# OledBoardV3.net
KiCad netlist of a schematic drawn in EAGLE
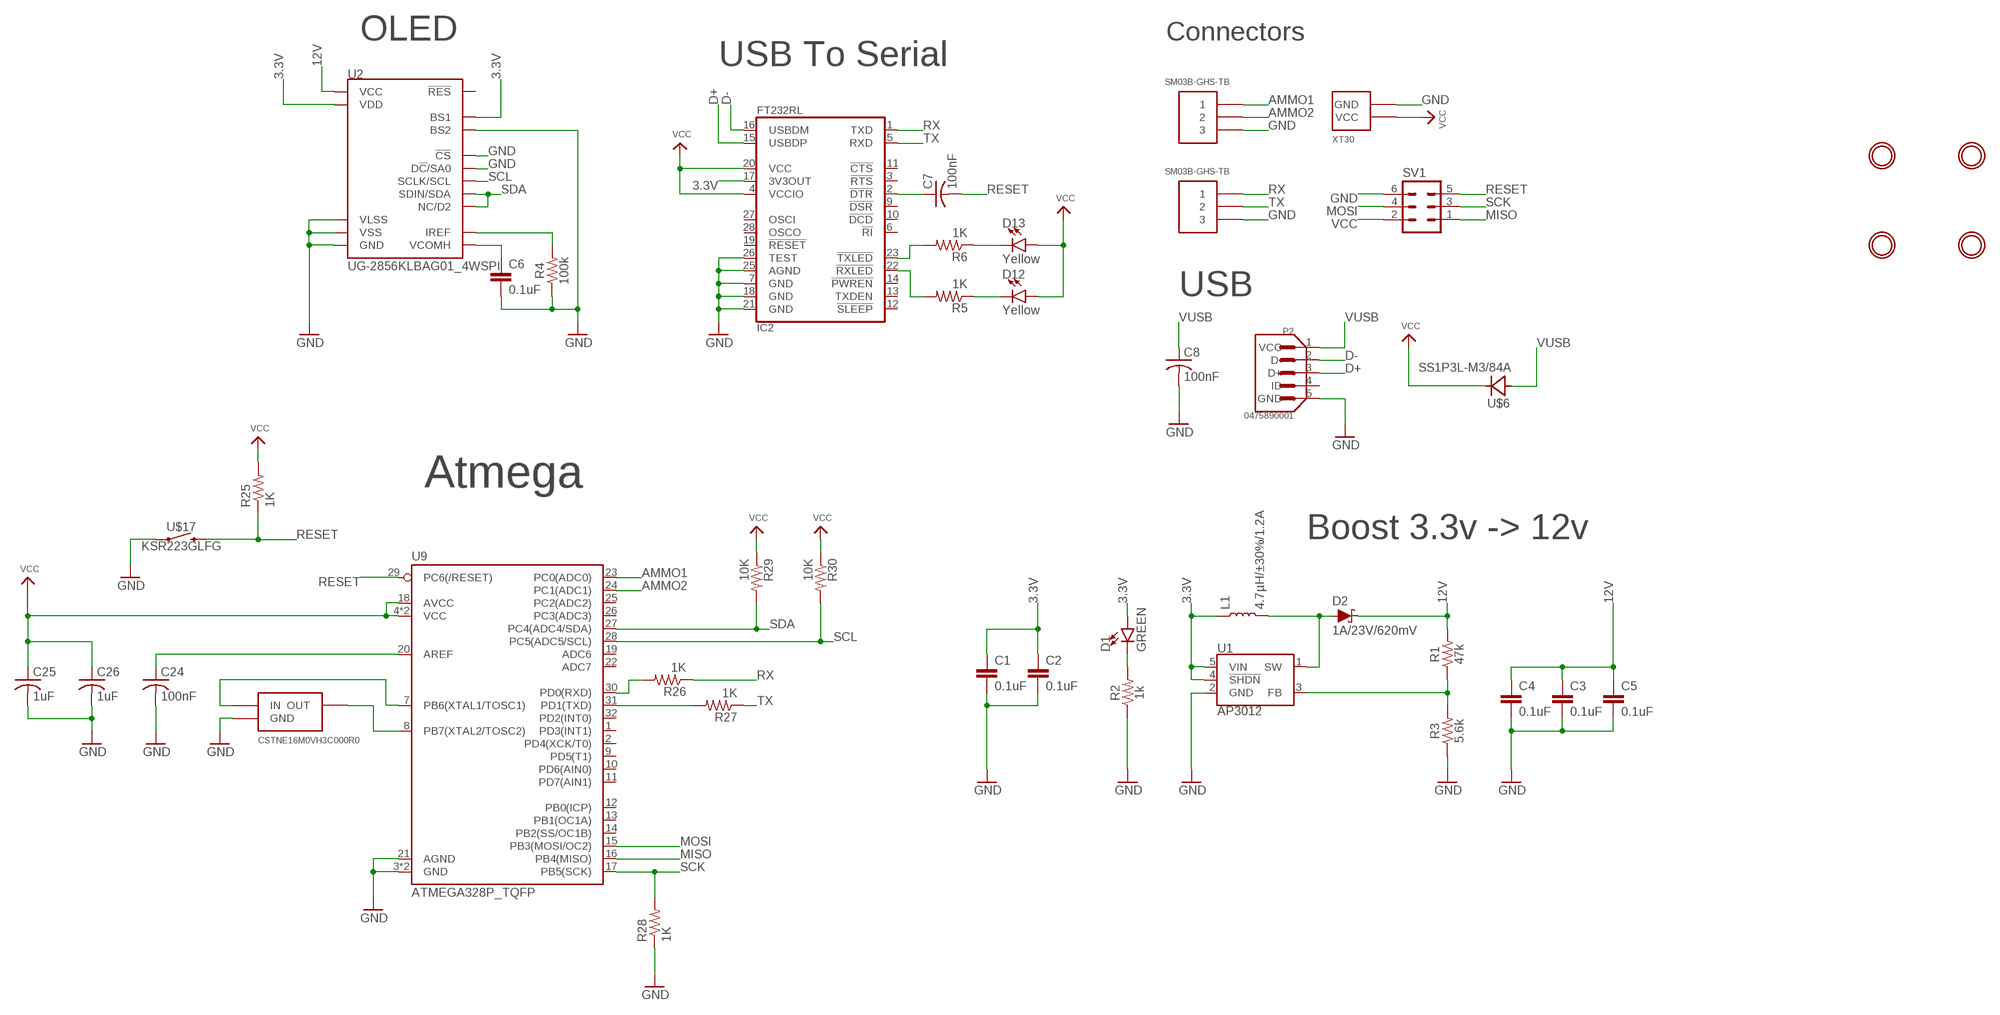
[diagram p0: schematic, sheet 1]

(export (version "E")
  (design (tool "Eeschema 10.0.6"))
  (components
    (comp (ref "C1")
      (value "0.1uF")
      (footprint "eagle-import:0603")
      (libsource (lib "eagle-import") (part "0.1UF-0603-25V-(+80/-20%)"))
    )
    (comp (ref "C2")
      (value "0.1uF")
      (footprint "eagle-import:0603")
      (libsource (lib "eagle-import") (part "0.1UF-0603-25V-(+80/-20%)"))
    )
    (comp (ref "C3")
      (value "0.1uF")
      (footprint "eagle-import:0603")
      (libsource (lib "eagle-import") (part "0.1UF-0603-25V-(+80/-20%)"))
    )
    (comp (ref "C4")
      (value "0.1uF")
      (footprint "eagle-import:0603")
      (libsource (lib "eagle-import") (part "0.1UF-0603-25V-(+80/-20%)"))
    )
    (comp (ref "C5")
      (value "0.1uF")
      (footprint "eagle-import:0603")
      (libsource (lib "eagle-import") (part "0.1UF-0603-25V-(+80/-20%)"))
    )
    (comp (ref "C6")
      (value "0.1uF")
      (footprint "eagle-import:0603")
      (libsource (lib "eagle-import") (part "0.1UF-0603-25V-(+80/-20%)"))
    )
    (comp (ref "C7")
      (value "100nF")
      (footprint "eagle-import:C0603")
      (libsource (lib "eagle-import") (part "C-USC0603"))
    )
    (comp (ref "C8")
      (value "100nF")
      (footprint "eagle-import:C0603")
      (libsource (lib "eagle-import") (part "C-USC0603"))
    )
    (comp (ref "C24")
      (value "100nF")
      (footprint "eagle-import:C0603")
      (libsource (lib "eagle-import") (part "C-USC0603"))
    )
    (comp (ref "C25")
      (value "1uF")
      (footprint "eagle-import:C0603")
      (libsource (lib "eagle-import") (part "C-USC0603"))
    )
    (comp (ref "C26")
      (value "1uF")
      (footprint "eagle-import:C0603")
      (libsource (lib "eagle-import") (part "C-USC0603"))
    )
    (comp (ref "D1")
      (value "GREEN")
      (footprint "eagle-import:LED-0603")
      (libsource (lib "eagle-import") (part "SparkFun-LED_529_LED0603"))
    )
    (comp (ref "D2")
      (value "1A/23V/620mV")
      (footprint "eagle-import:SOD-323")
      (libsource (lib "eagle-import") (part "DIODE-SCHOTTKY-BAT20J"))
    )
    (comp (ref "D12")
      (value "Yellow")
      (footprint "eagle-import:LED-0603")
      (libsource (lib "eagle-import") (part "LED0603"))
    )
    (comp (ref "D13")
      (value "Yellow")
      (footprint "eagle-import:LED-0603")
      (libsource (lib "eagle-import") (part "LED0603"))
    )
    (comp (ref "IC2")
      (value "FT232RL")
      (footprint "eagle-import:SSOP28-LD")
      (fields (field (name "DIGI-KEY_PART_NUMBER") "768-1007-1-ND") (field (name "MF") "FTDI, Future"))
      (libsource (lib "eagle-import") (part "FT232RL"))
    )
    (comp (ref "L1")
      (value "4.7µH/±30%/1.2A")
      (footprint "eagle-import:INDUCTOR_4.7UH")
      (libsource (lib "eagle-import") (part "INDUCTOR-CDRH-4.7UH"))
    )
    (comp (ref "P2")
      (value "0475890001")
      (footprint "eagle-import:MOLEX_0475890001")
      (fields (field (name "DIGI-KEY_PART_NUMBER") "WM17143CT-ND") (field (name "MF") "Molex"))
      (libsource (lib "eagle-import") (part "0475890001"))
    )
    (comp (ref "R1")
      (value "47k")
      (footprint "eagle-import:0603")
      (libsource (lib "eagle-import") (part "47KOHM-0603-1/10W-1%"))
    )
    (comp (ref "R2")
      (value "1k")
      (footprint "eagle-import:0603")
      (libsource (lib "eagle-import") (part "1KOHM-0603-1/10W-1%"))
    )
    (comp (ref "R3")
      (value "5.6k")
      (footprint "eagle-import:0603")
      (libsource (lib "eagle-import") (part "5.6KOHM-0603-1/10W-1%"))
    )
    (comp (ref "R4")
      (value "100k")
      (footprint "eagle-import:0603")
      (libsource (lib "eagle-import") (part "100KOHM-0603-1/10W-1%"))
    )
    (comp (ref "R5")
      (value "1K")
      (footprint "eagle-import:R0603")
      (libsource (lib "eagle-import") (part "R-US_R0603"))
    )
    (comp (ref "R6")
      (value "1K")
      (footprint "eagle-import:R0603")
      (libsource (lib "eagle-import") (part "R-US_R0603"))
    )
    (comp (ref "R25")
      (value "1K")
      (footprint "eagle-import:R0603")
      (libsource (lib "eagle-import") (part "R-US_R0603"))
    )
    (comp (ref "R26")
      (value "1K")
      (footprint "eagle-import:R0603")
      (libsource (lib "eagle-import") (part "R-US_R0603"))
    )
    (comp (ref "R27")
      (value "1K")
      (footprint "eagle-import:R0603")
      (libsource (lib "eagle-import") (part "R-US_R0603"))
    )
    (comp (ref "R28")
      (value "1K")
      (footprint "eagle-import:R0603")
      (libsource (lib "eagle-import") (part "R-US_R0603"))
    )
    (comp (ref "R29")
      (value "10K")
      (footprint "eagle-import:R0603")
      (libsource (lib "eagle-import") (part "R-US_R0603"))
    )
    (comp (ref "R30")
      (value "10K")
      (footprint "eagle-import:R0603")
      (libsource (lib "eagle-import") (part "R-US_R0603"))
    )
    (comp (ref "SV1")
      (value "MA03-2")
      (footprint "eagle-import:MA03-2")
      (libsource (lib "eagle-import") (part "MA03-2"))
    )
    (comp (ref "U$1")
      (value "MOUNTINGHOLE2.5")
      (footprint "eagle-import:MOUNTINGHOLE_2.5_PLATED")
      (libsource (lib "eagle-import") (part "MOUNTINGHOLE2.5"))
    )
    (comp (ref "U$2")
      (value "MOUNTINGHOLE2.5")
      (footprint "eagle-import:MOUNTINGHOLE_2.5_PLATED")
      (libsource (lib "eagle-import") (part "MOUNTINGHOLE2.5"))
    )
    (comp (ref "U$3")
      (value "MOUNTINGHOLE2.5")
      (footprint "eagle-import:MOUNTINGHOLE_2.5_PLATED")
      (libsource (lib "eagle-import") (part "MOUNTINGHOLE2.5"))
    )
    (comp (ref "U$4")
      (value "MOUNTINGHOLE2.5")
      (footprint "eagle-import:MOUNTINGHOLE_2.5_PLATED")
      (libsource (lib "eagle-import") (part "MOUNTINGHOLE2.5"))
    )
    (comp (ref "U$5")
      (value "SM03B-GHS-TB")
      (footprint "eagle-import:SM03B-GHS-TB")
      (libsource (lib "eagle-import") (part "SM03B-GHS-TB"))
    )
    (comp (ref "U$6")
      (value "SS1P3L-M3/84A")
      (footprint "eagle-import:SS1P3L-M3_84A")
      (libsource (lib "eagle-import") (part "SS1P3L-M3/84A"))
    )
    (comp (ref "U$8")
      (value "SM03B-GHS-TB")
      (footprint "eagle-import:SM03B-GHS-TB")
      (libsource (lib "eagle-import") (part "SM03B-GHS-TB"))
    )
    (comp (ref "U$9")
      (value "XT30PW-M")
      (footprint "eagle-import:XT30")
      (libsource (lib "eagle-import") (part "XT30PW-M"))
    )
    (comp (ref "U$16")
      (value "CSTNE16M0VH3C000R0")
      (footprint "eagle-import:CSTNE16M0VH3C000R0")
      (libsource (lib "eagle-import") (part "CSTNE16M0VH3C000R0"))
    )
    (comp (ref "U$17")
      (value "KSR223GLFG")
      (footprint "eagle-import:KSR223GLFG")
      (libsource (lib "eagle-import") (part "KSR223GLFG"))
    )
    (comp (ref "U1")
      (value "AP3012")
      (footprint "eagle-import:SOT23-5")
      (libsource (lib "eagle-import") (part "AP3012"))
    )
    (comp (ref "U2")
      (value "UG-2856KLBAG01_4WSPI")
      (footprint "eagle-import:FPC05024-42201")
      (libsource (lib "eagle-import") (part "UG-2856KLBAG01_4WSPI"))
    )
    (comp (ref "U9")
      (value "ATMEGA328P_TQFP")
      (footprint "eagle-import:TQFP32-08")
      (libsource (lib "eagle-import") (part "ATMEGA328P_TQFP"))
    )
  )
  (nets
    (net (code "1") (name "/3.3V") (class "Default")
      (node (ref "C1") (pin "1") (pinfunction "1_1") (pintype "passive"))
      (node (ref "C2") (pin "1") (pinfunction "1_1") (pintype "passive"))
      (node (ref "D1") (pin "A") (pinfunction "A_A") (pintype "passive"))
      (node (ref "IC2") (pin "17") (pinfunction "3V3OUT_17") (pintype "power_in"))
      (node (ref "L1") (pin "P$1") (pinfunction "1_P$1") (pintype "passive"))
      (node (ref "U1") (pin "4") (pinfunction "~{SHDN}_4") (pintype "bidirectional"))
      (node (ref "U1") (pin "5") (pinfunction "VIN_5") (pintype "bidirectional"))
      (node (ref "U2") (pin "P$5") (pinfunction "VDD_P$5") (pintype "bidirectional"))
      (node (ref "U2") (pin "P$6") (pinfunction "BS1_P$6") (pintype "bidirectional"))
    )
    (net (code "2") (name "/12V") (class "Default")
      (node (ref "C3") (pin "1") (pinfunction "1_1") (pintype "passive"))
      (node (ref "C4") (pin "1") (pinfunction "1_1") (pintype "passive"))
      (node (ref "C5") (pin "1") (pinfunction "1_1") (pintype "passive"))
      (node (ref "D2") (pin "C") (pinfunction "C_C") (pintype "passive"))
      (node (ref "R1") (pin "2") (pinfunction "2_2") (pintype "passive"))
      (node (ref "U2") (pin "P$23") (pinfunction "VCC_P$23") (pintype "bidirectional"))
    )
    (net (code "3") (name "/AMMO1") (class "Default")
      (node (ref "U$5") (pin "P$3") (pinfunction "1_P$3") (pintype "bidirectional"))
      (node (ref "U9") (pin "23") (pinfunction "PC0(ADC0)_23") (pintype "bidirectional"))
    )
    (net (code "4") (name "/AMMO2") (class "Default")
      (node (ref "U$5") (pin "P$4") (pinfunction "2_P$4") (pintype "bidirectional"))
      (node (ref "U9") (pin "24") (pinfunction "PC1(ADC1)_24") (pintype "bidirectional"))
    )
    (net (code "5") (name "/D+") (class "Default")
      (node (ref "IC2") (pin "15") (pinfunction "USBDP_15") (pintype "bidirectional"))
      (node (ref "P2") (pin "3") (pinfunction "D+_3") (pintype "bidirectional"))
    )
    (net (code "6") (name "/D-") (class "Default")
      (node (ref "IC2") (pin "16") (pinfunction "USBDM_16") (pintype "bidirectional"))
      (node (ref "P2") (pin "2") (pinfunction "D-_2") (pintype "bidirectional"))
    )
    (net (code "7") (name "/MISO") (class "Default")
      (node (ref "SV1") (pin "1") (pinfunction "1_1") (pintype "passive"))
      (node (ref "U9") (pin "16") (pinfunction "PB4(MISO)_16") (pintype "bidirectional"))
    )
    (net (code "8") (name "/MOSI") (class "Default")
      (node (ref "SV1") (pin "4") (pinfunction "4_4") (pintype "passive"))
      (node (ref "U9") (pin "15") (pinfunction "PB3(MOSI/OC2)_15") (pintype "bidirectional"))
    )
    (net (code "9") (name "/RESET") (class "Default")
      (node (ref "C7") (pin "2") (pinfunction "2_2") (pintype "passive"))
      (node (ref "R25") (pin "1") (pinfunction "1_1") (pintype "passive"))
      (node (ref "SV1") (pin "5") (pinfunction "5_5") (pintype "passive"))
      (node (ref "U$17") (pin "P$2") (pinfunction "2_P$2") (pintype "passive"))
      (node (ref "U9") (pin "29") (pinfunction "PC6(/RESET)_29") (pintype "bidirectional"))
    )
    (net (code "10") (name "/RX") (class "Default")
      (node (ref "IC2") (pin "1") (pinfunction "TXD_1") (pintype "output"))
      (node (ref "R26") (pin "1") (pinfunction "1_1") (pintype "passive"))
      (node (ref "U$8") (pin "P$3") (pinfunction "1_P$3") (pintype "bidirectional"))
    )
    (net (code "11") (name "/SCK") (class "Default")
      (node (ref "R28") (pin "2") (pinfunction "2_2") (pintype "passive"))
      (node (ref "SV1") (pin "3") (pinfunction "3_3") (pintype "passive"))
      (node (ref "U9") (pin "17") (pinfunction "PB5(SCK)_17") (pintype "bidirectional"))
    )
    (net (code "12") (name "/SCL") (class "Default")
      (node (ref "R30") (pin "2") (pinfunction "2_2") (pintype "passive"))
      (node (ref "U2") (pin "P$13") (pinfunction "SCLK/SCL_P$13") (pintype "bidirectional"))
      (node (ref "U9") (pin "28") (pinfunction "PC5(ADC5/SCL)_28") (pintype "bidirectional"))
    )
    (net (code "13") (name "/SDA") (class "Default")
      (node (ref "R29") (pin "2") (pinfunction "2_2") (pintype "passive"))
      (node (ref "U2") (pin "P$14") (pinfunction "SDIN/SDA_P$14") (pintype "bidirectional"))
      (node (ref "U2") (pin "P$15") (pinfunction "NC/D2_P$15") (pintype "bidirectional"))
      (node (ref "U9") (pin "27") (pinfunction "PC4(ADC4/SDA)_27") (pintype "bidirectional"))
    )
    (net (code "14") (name "/TX") (class "Default")
      (node (ref "IC2") (pin "5") (pinfunction "RXD_5") (pintype "input"))
      (node (ref "R27") (pin "1") (pinfunction "1_1") (pintype "passive"))
      (node (ref "U$8") (pin "P$4") (pinfunction "2_P$4") (pintype "bidirectional"))
    )
    (net (code "15") (name "/VUSB") (class "Default")
      (node (ref "C8") (pin "1") (pinfunction "1_1") (pintype "passive"))
      (node (ref "P2") (pin "1") (pinfunction "VCC_1") (pintype "power_in"))
      (node (ref "U$6") (pin "P$2") (pinfunction "A_P$2") (pintype "passive"))
    )
    (net (code "16") (name "GND") (class "Default")
      (node (ref "C1") (pin "2") (pinfunction "2_2") (pintype "passive"))
      (node (ref "C2") (pin "2") (pinfunction "2_2") (pintype "passive"))
      (node (ref "C24") (pin "2") (pinfunction "2_2") (pintype "passive"))
      (node (ref "C25") (pin "2") (pinfunction "2_2") (pintype "passive"))
      (node (ref "C26") (pin "2") (pinfunction "2_2") (pintype "passive"))
      (node (ref "C3") (pin "2") (pinfunction "2_2") (pintype "passive"))
      (node (ref "C4") (pin "2") (pinfunction "2_2") (pintype "passive"))
      (node (ref "C5") (pin "2") (pinfunction "2_2") (pintype "passive"))
      (node (ref "C6") (pin "2") (pinfunction "2_2") (pintype "passive"))
      (node (ref "C8") (pin "2") (pinfunction "2_2") (pintype "passive"))
      (node (ref "IC2") (pin "18") (pinfunction "GND_18") (pintype "power_in"))
      (node (ref "IC2") (pin "21") (pinfunction "GND_21") (pintype "power_in"))
      (node (ref "IC2") (pin "25") (pinfunction "AGND_25") (pintype "power_in"))
      (node (ref "IC2") (pin "26") (pinfunction "TEST_26") (pintype "input"))
      (node (ref "IC2") (pin "7") (pinfunction "GND_7") (pintype "power_in"))
      (node (ref "P2") (pin "5") (pinfunction "GND_5") (pintype "power_in"))
      (node (ref "R2") (pin "1") (pinfunction "1_1") (pintype "passive"))
      (node (ref "R28") (pin "1") (pinfunction "1_1") (pintype "passive"))
      (node (ref "R3") (pin "1") (pinfunction "1_1") (pintype "passive"))
      (node (ref "R4") (pin "1") (pinfunction "1_1") (pintype "passive"))
      (node (ref "SV1") (pin "6") (pinfunction "6_6") (pintype "passive"))
      (node (ref "U$16") (pin "2") (pinfunction "GND_2") (pintype "bidirectional"))
      (node (ref "U$17") (pin "P$1") (pinfunction "1_P$1") (pintype "passive"))
      (node (ref "U$5") (pin "P$5") (pinfunction "3_P$5") (pintype "bidirectional"))
      (node (ref "U$8") (pin "P$5") (pinfunction "3_P$5") (pintype "bidirectional"))
      (node (ref "U$9") (pin "P$2") (pinfunction "GND_P$2") (pintype "bidirectional"))
      (node (ref "U1") (pin "2") (pinfunction "GND_2") (pintype "bidirectional"))
      (node (ref "U2") (pin "P$1") (pinfunction "GND_P$1") (pintype "bidirectional"))
      (node (ref "U2") (pin "P$10") (pinfunction "D~{C}/SA0_P$10") (pintype "bidirectional"))
      (node (ref "U2") (pin "P$11") (pinfunction "GND_P$11") (pintype "bidirectional"))
      (node (ref "U2") (pin "P$12") (pinfunction "GND_P$12") (pintype "bidirectional"))
      (node (ref "U2") (pin "P$16") (pinfunction "GND_P$16") (pintype "bidirectional"))
      (node (ref "U2") (pin "P$17") (pinfunction "GND_P$17") (pintype "bidirectional"))
      (node (ref "U2") (pin "P$18") (pinfunction "GND_P$18") (pintype "bidirectional"))
      (node (ref "U2") (pin "P$19") (pinfunction "GND_P$19") (pintype "bidirectional"))
      (node (ref "U2") (pin "P$2") (pinfunction "VLSS_P$2") (pintype "bidirectional"))
      (node (ref "U2") (pin "P$20") (pinfunction "GND_P$20") (pintype "bidirectional"))
      (node (ref "U2") (pin "P$24") (pinfunction "GND_P$24") (pintype "bidirectional"))
      (node (ref "U2") (pin "P$3") (pinfunction "VSS_P$3") (pintype "bidirectional"))
      (node (ref "U2") (pin "P$7") (pinfunction "BS2_P$7") (pintype "bidirectional"))
      (node (ref "U2") (pin "P$8") (pinfunction "~{CS}_P$8") (pintype "bidirectional"))
      (node (ref "U9") (pin "21") (pinfunction "AGND_21") (pintype "bidirectional"))
      (node (ref "U9") (pin "3") (pinfunction "GND_3") (pintype "bidirectional"))
      (node (ref "U9") (pin "5") (pinfunction "GND_5") (pintype "bidirectional"))
    )
    (net (code "17") (name "Net-(D1-PadC)") (class "Default")
      (node (ref "D1") (pin "C") (pinfunction "C_C") (pintype "passive"))
      (node (ref "R2") (pin "2") (pinfunction "2_2") (pintype "passive"))
    )
    (net (code "18") (name "Net-(D12-PadC)") (class "Default")
      (node (ref "D12") (pin "C") (pinfunction "C_C") (pintype "passive"))
      (node (ref "R5") (pin "1") (pinfunction "1_1") (pintype "passive"))
    )
    (net (code "19") (name "Net-(D13-PadC)") (class "Default")
      (node (ref "D13") (pin "C") (pinfunction "C_C") (pintype "passive"))
      (node (ref "R6") (pin "1") (pinfunction "1_1") (pintype "passive"))
    )
    (net (code "20") (name "Net-(IC2-~{DTR})") (class "Default")
      (node (ref "C7") (pin "1") (pinfunction "1_1") (pintype "passive"))
      (node (ref "IC2") (pin "2") (pinfunction "~{DTR}_2") (pintype "output"))
    )
    (net (code "21") (name "Net-(IC2-~{RXLED})") (class "Default")
      (node (ref "IC2") (pin "22") (pinfunction "~{RXLED}_22") (pintype "input"))
      (node (ref "R5") (pin "2") (pinfunction "2_2") (pintype "passive"))
    )
    (net (code "22") (name "Net-(IC2-~{TXLED})") (class "Default")
      (node (ref "IC2") (pin "23") (pinfunction "~{TXLED}_23") (pintype "input"))
      (node (ref "R6") (pin "2") (pinfunction "2_2") (pintype "passive"))
    )
    (net (code "23") (name "Net-(L1-2)") (class "Default")
      (node (ref "D2") (pin "A") (pinfunction "A_A") (pintype "passive"))
      (node (ref "L1") (pin "P$2") (pinfunction "2_P$2") (pintype "passive"))
      (node (ref "U1") (pin "1") (pinfunction "SW_1") (pintype "bidirectional"))
    )
    (net (code "24") (name "Net-(U$16-IN)") (class "Default")
      (node (ref "U$16") (pin "1") (pinfunction "IN_1") (pintype "bidirectional"))
      (node (ref "U9") (pin "7") (pinfunction "PB6(XTAL1/TOSC1)_7") (pintype "bidirectional"))
    )
    (net (code "25") (name "Net-(U$16-OUT)") (class "Default")
      (node (ref "U$16") (pin "3") (pinfunction "OUT_3") (pintype "bidirectional"))
      (node (ref "U9") (pin "8") (pinfunction "PB7(XTAL2/TOSC2)_8") (pintype "bidirectional"))
    )
    (net (code "26") (name "Net-(U1-FB)") (class "Default")
      (node (ref "R1") (pin "1") (pinfunction "1_1") (pintype "passive"))
      (node (ref "R3") (pin "2") (pinfunction "2_2") (pintype "passive"))
      (node (ref "U1") (pin "3") (pinfunction "FB_3") (pintype "bidirectional"))
    )
    (net (code "27") (name "Net-(U2-IREF)") (class "Default")
      (node (ref "R4") (pin "2") (pinfunction "2_2") (pintype "passive"))
      (node (ref "U2") (pin "P$21") (pinfunction "IREF_P$21") (pintype "bidirectional"))
    )
    (net (code "28") (name "Net-(U2-VCOMH)") (class "Default")
      (node (ref "C6") (pin "1") (pinfunction "1_1") (pintype "passive"))
      (node (ref "U2") (pin "P$22") (pinfunction "VCOMH_P$22") (pintype "bidirectional"))
    )
    (net (code "29") (name "Net-(U9-AREF)") (class "Default")
      (node (ref "C24") (pin "1") (pinfunction "1_1") (pintype "passive"))
      (node (ref "U9") (pin "20") (pinfunction "AREF_20") (pintype "bidirectional"))
    )
    (net (code "30") (name "Net-(U9-PD0(RXD))") (class "Default")
      (node (ref "R26") (pin "2") (pinfunction "2_2") (pintype "passive"))
      (node (ref "U9") (pin "30") (pinfunction "PD0(RXD)_30") (pintype "bidirectional"))
    )
    (net (code "31") (name "Net-(U9-PD1(TXD))") (class "Default")
      (node (ref "R27") (pin "2") (pinfunction "2_2") (pintype "passive"))
      (node (ref "U9") (pin "31") (pinfunction "PD1(TXD)_31") (pintype "bidirectional"))
    )
    (net (code "32") (name "VCC") (class "Default")
      (node (ref "C25") (pin "1") (pinfunction "1_1") (pintype "passive"))
      (node (ref "C26") (pin "1") (pinfunction "1_1") (pintype "passive"))
      (node (ref "D12") (pin "A") (pinfunction "A_A") (pintype "passive"))
      (node (ref "D13") (pin "A") (pinfunction "A_A") (pintype "passive"))
      (node (ref "IC2") (pin "20") (pinfunction "VCC_20") (pintype "power_in"))
      (node (ref "IC2") (pin "4") (pinfunction "VCCIO_4") (pintype "power_in"))
      (node (ref "R25") (pin "2") (pinfunction "2_2") (pintype "passive"))
      (node (ref "R29") (pin "1") (pinfunction "1_1") (pintype "passive"))
      (node (ref "R30") (pin "1") (pinfunction "1_1") (pintype "passive"))
      (node (ref "SV1") (pin "2") (pinfunction "2_2") (pintype "passive"))
      (node (ref "U$6") (pin "P$1") (pinfunction "C_P$1") (pintype "passive"))
      (node (ref "U$9") (pin "P$1") (pinfunction "VCC_P$1") (pintype "bidirectional"))
      (node (ref "U9") (pin "18") (pinfunction "AVCC_18") (pintype "bidirectional"))
      (node (ref "U9") (pin "4") (pinfunction "VCC_4") (pintype "bidirectional"))
      (node (ref "U9") (pin "6") (pinfunction "VCC_6") (pintype "bidirectional"))
    )
    (net (code "33") (name "unconnected-(IC2-OSCI-Pad27)") (class "Default")
      (node (ref "IC2") (pin "27") (pinfunction "OSCI_27") (pintype "no_connect"))
    )
    (net (code "34") (name "unconnected-(IC2-OSCO-Pad28)") (class "Default")
      (node (ref "IC2") (pin "28") (pinfunction "OSCO_28") (pintype "output"))
    )
    (net (code "35") (name "unconnected-(IC2-TXDEN-Pad13)") (class "Default")
      (node (ref "IC2") (pin "13") (pinfunction "TXDEN_13") (pintype "no_connect"))
    )
    (net (code "36") (name "unconnected-(IC2-~{CTS}-Pad11)") (class "Default")
      (node (ref "IC2") (pin "11") (pinfunction "~{CTS}_11") (pintype "input"))
    )
    (net (code "37") (name "unconnected-(IC2-~{DCD}-Pad10)") (class "Default")
      (node (ref "IC2") (pin "10") (pinfunction "~{DCD}_10") (pintype "no_connect"))
    )
    (net (code "38") (name "unconnected-(IC2-~{DSR}-Pad9)") (class "Default")
      (node (ref "IC2") (pin "9") (pinfunction "~{DSR}_9") (pintype "no_connect"))
    )
    (net (code "39") (name "unconnected-(IC2-~{PWREN}-Pad14)") (class "Default")
      (node (ref "IC2") (pin "14") (pinfunction "~{PWREN}_14") (pintype "no_connect"))
    )
    (net (code "40") (name "unconnected-(IC2-~{RESET}-Pad19)") (class "Default")
      (node (ref "IC2") (pin "19") (pinfunction "~{RESET}_19") (pintype "no_connect"))
    )
    (net (code "41") (name "unconnected-(IC2-~{RI}-Pad6)") (class "Default")
      (node (ref "IC2") (pin "6") (pinfunction "~{RI}_6") (pintype "no_connect"))
    )
    (net (code "42") (name "unconnected-(IC2-~{RTS}-Pad3)") (class "Default")
      (node (ref "IC2") (pin "3") (pinfunction "~{RTS}_3") (pintype "output"))
    )
    (net (code "43") (name "unconnected-(IC2-~{SLEEP}-Pad12)") (class "Default")
      (node (ref "IC2") (pin "12") (pinfunction "~{SLEEP}_12") (pintype "no_connect"))
    )
    (net (code "44") (name "unconnected-(P2-ID-Pad4)") (class "Default")
      (node (ref "P2") (pin "4") (pinfunction "ID_4") (pintype "bidirectional"))
    )
    (net (code "45") (name "unconnected-(U2-~{RES}-PadP$9)") (class "Default")
      (node (ref "U2") (pin "P$9") (pinfunction "~{RES}_P$9") (pintype "bidirectional"))
    )
    (net (code "46") (name "unconnected-(U9-ADC6-Pad19)") (class "Default")
      (node (ref "U9") (pin "19") (pinfunction "ADC6_19") (pintype "bidirectional"))
    )
    (net (code "47") (name "unconnected-(U9-ADC7-Pad22)") (class "Default")
      (node (ref "U9") (pin "22") (pinfunction "ADC7_22") (pintype "bidirectional"))
    )
    (net (code "48") (name "unconnected-(U9-PB0(ICP)-Pad12)") (class "Default")
      (node (ref "U9") (pin "12") (pinfunction "PB0(ICP)_12") (pintype "bidirectional"))
    )
    (net (code "49") (name "unconnected-(U9-PB1(OC1A)-Pad13)") (class "Default")
      (node (ref "U9") (pin "13") (pinfunction "PB1(OC1A)_13") (pintype "bidirectional"))
    )
    (net (code "50") (name "unconnected-(U9-PB2(SS{slash}OC1B)-Pad14)") (class "Default")
      (node (ref "U9") (pin "14") (pinfunction "PB2(SS/OC1B)_14") (pintype "bidirectional"))
    )
    (net (code "51") (name "unconnected-(U9-PC2(ADC2)-Pad25)") (class "Default")
      (node (ref "U9") (pin "25") (pinfunction "PC2(ADC2)_25") (pintype "bidirectional"))
    )
    (net (code "52") (name "unconnected-(U9-PC3(ADC3)-Pad26)") (class "Default")
      (node (ref "U9") (pin "26") (pinfunction "PC3(ADC3)_26") (pintype "bidirectional"))
    )
    (net (code "53") (name "unconnected-(U9-PD2(INT0)-Pad32)") (class "Default")
      (node (ref "U9") (pin "32") (pinfunction "PD2(INT0)_32") (pintype "bidirectional"))
    )
    (net (code "54") (name "unconnected-(U9-PD3(INT1)-Pad1)") (class "Default")
      (node (ref "U9") (pin "1") (pinfunction "PD3(INT1)_1") (pintype "bidirectional"))
    )
    (net (code "55") (name "unconnected-(U9-PD4(XCK{slash}T0)-Pad2)") (class "Default")
      (node (ref "U9") (pin "2") (pinfunction "PD4(XCK/T0)_2") (pintype "bidirectional"))
    )
    (net (code "56") (name "unconnected-(U9-PD5(T1)-Pad9)") (class "Default")
      (node (ref "U9") (pin "9") (pinfunction "PD5(T1)_9") (pintype "bidirectional"))
    )
    (net (code "57") (name "unconnected-(U9-PD6(AIN0)-Pad10)") (class "Default")
      (node (ref "U9") (pin "10") (pinfunction "PD6(AIN0)_10") (pintype "bidirectional"))
    )
    (net (code "58") (name "unconnected-(U9-PD7(AIN1)-Pad11)") (class "Default")
      (node (ref "U9") (pin "11") (pinfunction "PD7(AIN1)_11") (pintype "bidirectional"))
    )
  )
)
